# aaXBee.net
KiCad netlist of a schematic drawn in EAGLE
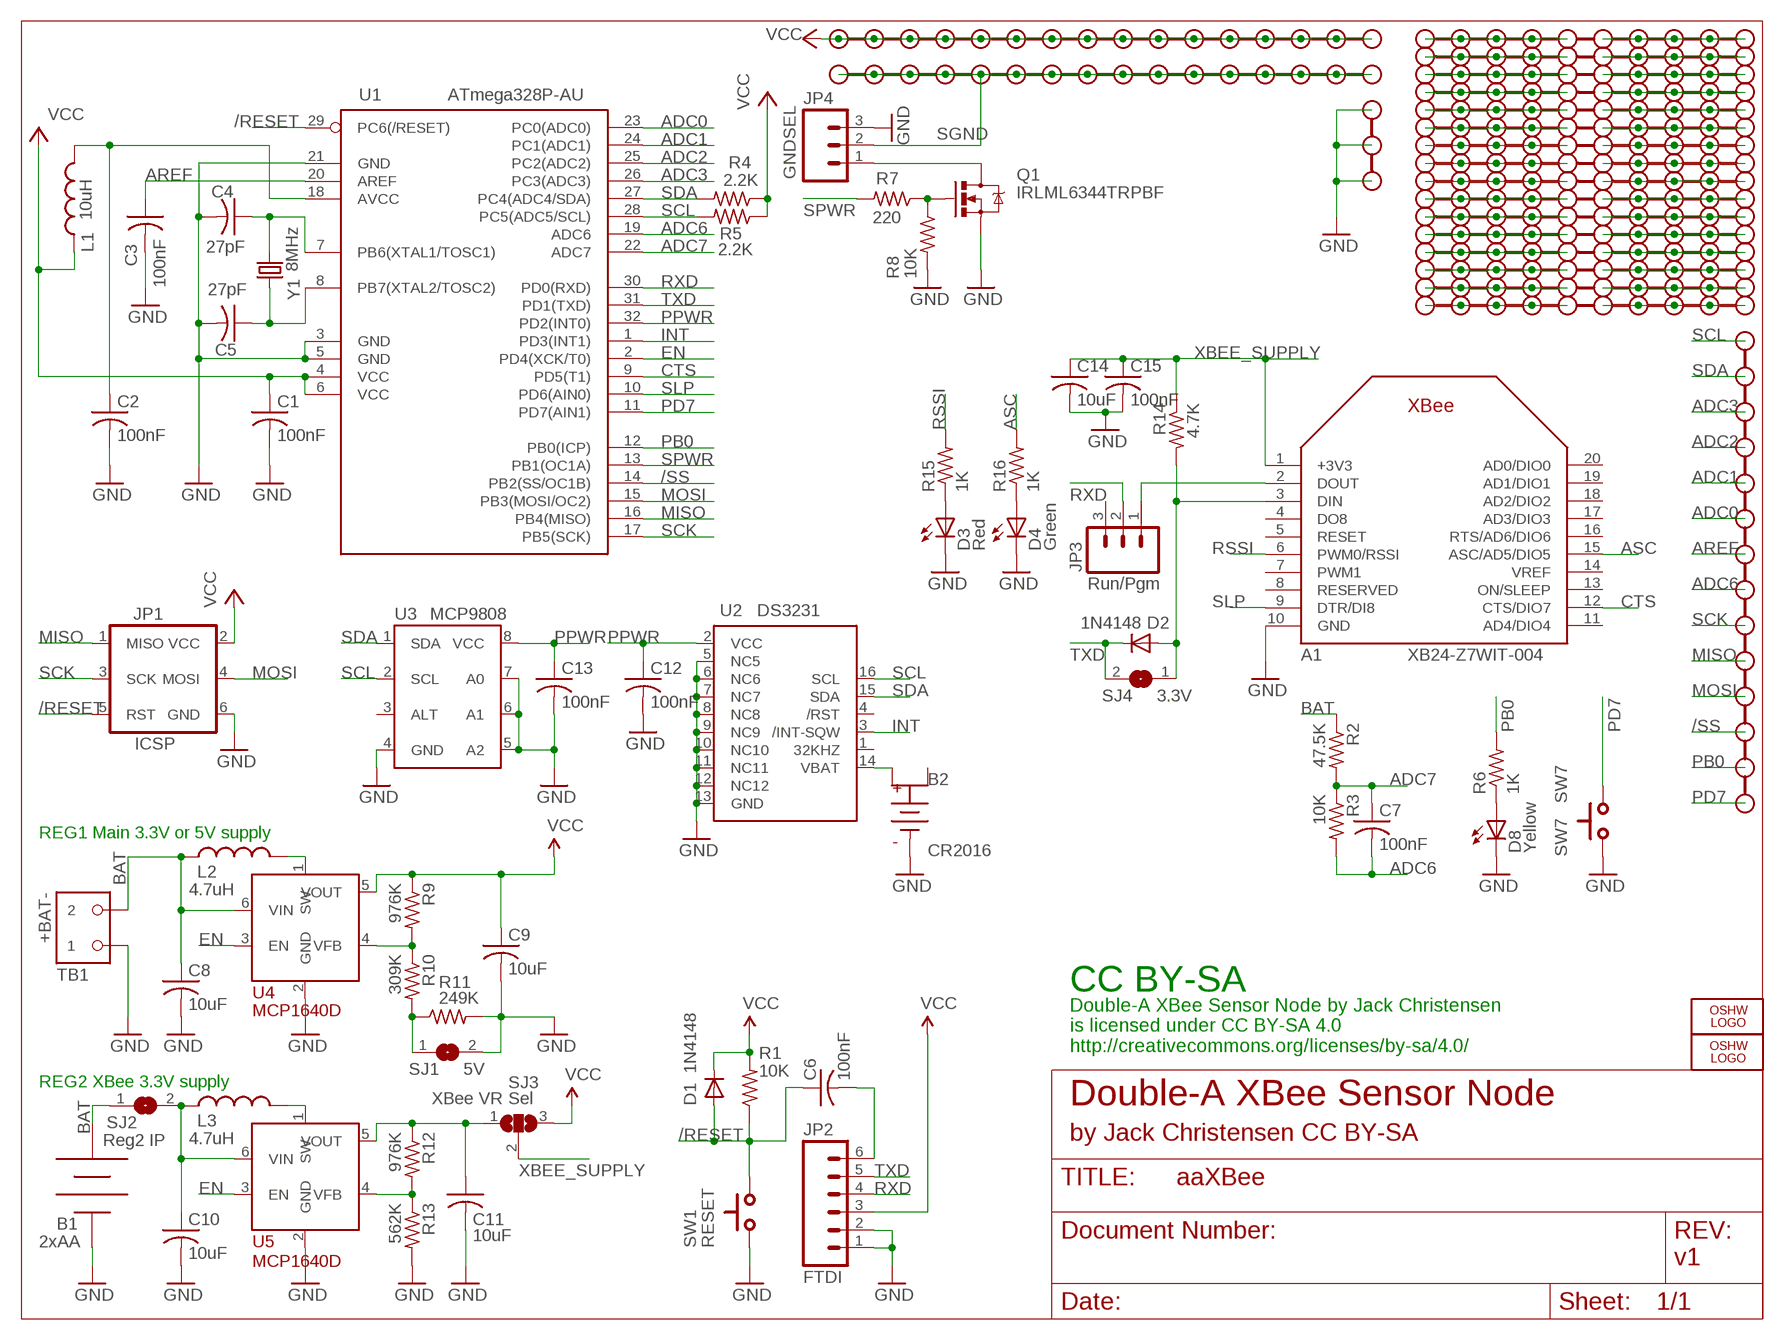
[diagram p0: schematic, sheet 1]

(export (version "E")
  (design (tool "Eeschema 10.0.6"))
  (components
    (comp (ref "A1")
      (value "XB24-Z7WIT-004")
      (footprint "eagle-import:XBEE_OVAL_PADS")
      (libsource (lib "eagle-import") (part "ULINK_XBEEOVALPADS"))
    )
    (comp (ref "B1")
      (value "2xAA")
      (footprint "eagle-import:KEYSTONE-2462-NO-HOLES")
      (libsource (lib "eagle-import") (part "BATTERY-2AANOHOLES"))
    )
    (comp (ref "B2")
      (value "CR2016")
      (footprint "eagle-import:BAT-HLD-002-SMT")
      (libsource (lib "eagle-import") (part "COIN-CELL-2016-SMT"))
    )
    (comp (ref "C1")
      (value "100nF")
      (footprint "eagle-import:M0805")
      (libsource (lib "eagle-import") (part "C-USM0805"))
    )
    (comp (ref "C2")
      (value "100nF")
      (footprint "eagle-import:M0805")
      (libsource (lib "eagle-import") (part "C-USM0805"))
    )
    (comp (ref "C3")
      (value "100nF")
      (footprint "eagle-import:M0805")
      (libsource (lib "eagle-import") (part "C-USM0805"))
    )
    (comp (ref "C4")
      (value "27pF")
      (footprint "eagle-import:M0805")
      (libsource (lib "eagle-import") (part "C-USM0805"))
    )
    (comp (ref "C5")
      (value "27pF")
      (footprint "eagle-import:M0805")
      (libsource (lib "eagle-import") (part "C-USM0805"))
    )
    (comp (ref "C6")
      (value "100nF")
      (footprint "eagle-import:M0805")
      (libsource (lib "eagle-import") (part "C-USM0805"))
    )
    (comp (ref "C7")
      (value "100nF")
      (footprint "eagle-import:M0805")
      (libsource (lib "eagle-import") (part "C-USM0805"))
    )
    (comp (ref "C8")
      (value "10uF")
      (footprint "eagle-import:M0805")
      (libsource (lib "eagle-import") (part "C-USM0805"))
    )
    (comp (ref "C9")
      (value "10uF")
      (footprint "eagle-import:M0805")
      (libsource (lib "eagle-import") (part "C-USM0805"))
    )
    (comp (ref "C10")
      (value "10uF")
      (footprint "eagle-import:M0805")
      (libsource (lib "eagle-import") (part "C-USM0805"))
    )
    (comp (ref "C11")
      (value "10uF")
      (footprint "eagle-import:M0805")
      (libsource (lib "eagle-import") (part "C-USM0805"))
    )
    (comp (ref "C12")
      (value "100nF")
      (footprint "eagle-import:M0805")
      (libsource (lib "eagle-import") (part "C-USM0805"))
    )
    (comp (ref "C13")
      (value "100nF")
      (footprint "eagle-import:M0805")
      (libsource (lib "eagle-import") (part "C-USM0805"))
    )
    (comp (ref "C14")
      (value "10uF")
      (footprint "eagle-import:M0805")
      (libsource (lib "eagle-import") (part "C-USM0805"))
    )
    (comp (ref "C15")
      (value "100nF")
      (footprint "eagle-import:M0805")
      (libsource (lib "eagle-import") (part "C-USM0805"))
    )
    (comp (ref "D1")
      (value "1N4148")
      (footprint "eagle-import:SOD-323F-A")
      (libsource (lib "eagle-import") (part "DIODESOD-323F-A"))
    )
    (comp (ref "D2")
      (value "1N4148")
      (footprint "eagle-import:SOD-323F-A")
      (libsource (lib "eagle-import") (part "DIODESOD-323F-A"))
    )
    (comp (ref "D3")
      (value "Red")
      (footprint "eagle-import:D0805A")
      (libsource (lib "eagle-import") (part "LEDD0805A"))
    )
    (comp (ref "D4")
      (value "Green")
      (footprint "eagle-import:D0805")
      (libsource (lib "eagle-import") (part "LEDD0805"))
    )
    (comp (ref "D8")
      (value "Yellow")
      (footprint "eagle-import:D0805A")
      (libsource (lib "eagle-import") (part "LEDD0805A"))
    )
    (comp (ref "JP1")
      (value "ICSP")
      (footprint "eagle-import:2X3_LOCK")
      (libsource (lib "eagle-import") (part "AVR_SPI_PRG_62X3_LOCK"))
    )
    (comp (ref "JP2")
      (value "FTDI")
      (footprint "eagle-import:1X06_LOCK")
      (libsource (lib "eagle-import") (part "M06LOCK"))
    )
    (comp (ref "JP3")
      (value "Run/Pgm")
      (footprint "eagle-import:1X03_LOCK")
      (libsource (lib "eagle-import") (part "M03LOCK"))
    )
    (comp (ref "JP4")
      (value "GNDSEL")
      (footprint "eagle-import:1X03_LOCK")
      (libsource (lib "eagle-import") (part "M03LOCK"))
    )
    (comp (ref "L1")
      (value "10uH")
      (footprint "eagle-import:M0805")
      (libsource (lib "eagle-import") (part "INDUCTORM0805"))
    )
    (comp (ref "L2")
      (value "4.7uH")
      (footprint "eagle-import:NRS4018")
      (libsource (lib "eagle-import") (part "INDUCTORNRS4018"))
    )
    (comp (ref "L3")
      (value "4.7uH")
      (footprint "eagle-import:NRS4018")
      (libsource (lib "eagle-import") (part "INDUCTORNRS4018"))
    )
    (comp (ref "LOGO1")
      (value "OSHW_LOGO_8MILX0150-NT")
      (footprint "eagle-import:OSHW_8X150_NOTEXT")
      (libsource (lib "eagle-import") (part "OSHW_LOGO_8MILX0150-NT"))
    )
    (comp (ref "LOGO2")
      (value "OSHW_LOGO_8MILX0150-NT")
      (footprint "eagle-import:OSHW_8X150_NOTEXT")
      (libsource (lib "eagle-import") (part "OSHW_LOGO_8MILX0150-NT"))
    )
    (comp (ref "PR1")
      (value "PROTO-10")
      (footprint "eagle-import:PROTO-10")
      (libsource (lib "eagle-import") (part "PROTO-10"))
    )
    (comp (ref "PR2")
      (value "PROTO-10")
      (footprint "eagle-import:PROTO-10")
      (libsource (lib "eagle-import") (part "PROTO-10"))
    )
    (comp (ref "PR3")
      (value "PROTO-10")
      (footprint "eagle-import:PROTO-10")
      (libsource (lib "eagle-import") (part "PROTO-10"))
    )
    (comp (ref "PR4")
      (value "PROTO-10")
      (footprint "eagle-import:PROTO-10")
      (libsource (lib "eagle-import") (part "PROTO-10"))
    )
    (comp (ref "PR5")
      (value "PROTO-10")
      (footprint "eagle-import:PROTO-10")
      (libsource (lib "eagle-import") (part "PROTO-10"))
    )
    (comp (ref "PR6")
      (value "PROTO-10")
      (footprint "eagle-import:PROTO-10")
      (libsource (lib "eagle-import") (part "PROTO-10"))
    )
    (comp (ref "PR7")
      (value "PROTO-10")
      (footprint "eagle-import:PROTO-10")
      (libsource (lib "eagle-import") (part "PROTO-10"))
    )
    (comp (ref "PR8")
      (value "PROTO-10")
      (footprint "eagle-import:PROTO-10")
      (libsource (lib "eagle-import") (part "PROTO-10"))
    )
    (comp (ref "PR9")
      (value "PROTO-10")
      (footprint "eagle-import:PROTO-10")
      (libsource (lib "eagle-import") (part "PROTO-10"))
    )
    (comp (ref "PR10")
      (value "PROTO-10")
      (footprint "eagle-import:PROTO-10")
      (libsource (lib "eagle-import") (part "PROTO-10"))
    )
    (comp (ref "PR11")
      (value "PROTO-10")
      (footprint "eagle-import:PROTO-10")
      (libsource (lib "eagle-import") (part "PROTO-10"))
    )
    (comp (ref "PR12")
      (value "PROTO-10")
      (footprint "eagle-import:PROTO-10")
      (libsource (lib "eagle-import") (part "PROTO-10"))
    )
    (comp (ref "PR13")
      (value "GND")
      (footprint "eagle-import:PROTO-3")
      (libsource (lib "eagle-import") (part "PROTO-3"))
    )
    (comp (ref "PR14")
      (value "PROTO-10")
      (footprint "eagle-import:PROTO-10")
      (libsource (lib "eagle-import") (part "PROTO-10"))
    )
    (comp (ref "PR15")
      (value "PROTO-10")
      (footprint "eagle-import:PROTO-10")
      (libsource (lib "eagle-import") (part "PROTO-10"))
    )
    (comp (ref "PR16")
      (value "PROTO-10")
      (footprint "eagle-import:PROTO-10")
      (libsource (lib "eagle-import") (part "PROTO-10"))
    )
    (comp (ref "PR17")
      (value "PROTO-10")
      (footprint "eagle-import:PROTO-10")
      (libsource (lib "eagle-import") (part "PROTO-10"))
    )
    (comp (ref "PR18")
      (value "Proto ground")
      (footprint "eagle-import:PROTO-16")
      (libsource (lib "eagle-import") (part "PROTO-16"))
    )
    (comp (ref "PR19")
      (value "Proto Vcc")
      (footprint "eagle-import:PROTO-16")
      (libsource (lib "eagle-import") (part "PROTO-16"))
    )
    (comp (ref "PR20")
      (value "Signals")
      (footprint "eagle-import:PROTO-14-NR")
      (libsource (lib "eagle-import") (part "PROTO-14NR"))
    )
    (comp (ref "Q1")
      (value "IRLML6344TRPBF")
      (footprint "eagle-import:SOT23")
      (libsource (lib "eagle-import") (part "MOSFET-NCHANNELSOT23"))
    )
    (comp (ref "R1")
      (value "10K")
      (footprint "eagle-import:M0805")
      (libsource (lib "eagle-import") (part "R-US_M0805"))
    )
    (comp (ref "R2")
      (value "47.5K")
      (footprint "eagle-import:M0805")
      (libsource (lib "eagle-import") (part "R-US_M0805"))
    )
    (comp (ref "R3")
      (value "10K")
      (footprint "eagle-import:M0805")
      (libsource (lib "eagle-import") (part "R-US_M0805"))
    )
    (comp (ref "R4")
      (value "2.2K")
      (footprint "eagle-import:M0805")
      (libsource (lib "eagle-import") (part "R-US_M0805"))
    )
    (comp (ref "R5")
      (value "2.2K")
      (footprint "eagle-import:M0805")
      (libsource (lib "eagle-import") (part "R-US_M0805"))
    )
    (comp (ref "R6")
      (value "1K")
      (footprint "eagle-import:M0805")
      (libsource (lib "eagle-import") (part "R-US_M0805"))
    )
    (comp (ref "R7")
      (value "220")
      (footprint "eagle-import:M0805")
      (libsource (lib "eagle-import") (part "R-US_M0805"))
    )
    (comp (ref "R8")
      (value "10K")
      (footprint "eagle-import:M0805")
      (libsource (lib "eagle-import") (part "R-US_M0805"))
    )
    (comp (ref "R9")
      (value "976K")
      (footprint "eagle-import:M0805")
      (libsource (lib "eagle-import") (part "R-US_M0805"))
    )
    (comp (ref "R10")
      (value "309K")
      (footprint "eagle-import:M0805")
      (libsource (lib "eagle-import") (part "R-US_M0805"))
    )
    (comp (ref "R11")
      (value "249K")
      (footprint "eagle-import:M0805")
      (libsource (lib "eagle-import") (part "R-US_M0805"))
    )
    (comp (ref "R12")
      (value "976K")
      (footprint "eagle-import:M0805")
      (libsource (lib "eagle-import") (part "R-US_M0805"))
    )
    (comp (ref "R13")
      (value "562K")
      (footprint "eagle-import:M0805")
      (libsource (lib "eagle-import") (part "R-US_M0805"))
    )
    (comp (ref "R14")
      (value "4.7K")
      (footprint "eagle-import:M0805")
      (libsource (lib "eagle-import") (part "R-US_M0805"))
    )
    (comp (ref "R15")
      (value "1K")
      (footprint "eagle-import:M0805")
      (libsource (lib "eagle-import") (part "R-US_M0805"))
    )
    (comp (ref "R16")
      (value "1K")
      (footprint "eagle-import:M0805")
      (libsource (lib "eagle-import") (part "R-US_M0805"))
    )
    (comp (ref "SJ1") (value "5V") (footprint "eagle-import:SJ") (libsource (lib "eagle-import") (part "SJ")))
    (comp (ref "SJ2")
      (value "Reg2 IP")
      (footprint "eagle-import:SJ")
      (libsource (lib "eagle-import") (part "SJ"))
    )
    (comp (ref "SJ3")
      (value "XBee VR Sel")
      (footprint "eagle-import:SJ_2")
      (libsource (lib "eagle-import") (part "SJ2W"))
    )
    (comp (ref "SJ4")
      (value "3.3V")
      (footprint "eagle-import:SJ")
      (libsource (lib "eagle-import") (part "SJ"))
    )
    (comp (ref "SW1")
      (value "RESET")
      (footprint "eagle-import:SWITCH-TACT-6X3.5-SMT")
      (libsource (lib "eagle-import") (part "SPST-NO-MCTACT-6X3.5-SMT"))
    )
    (comp (ref "SW7")
      (value "SW7")
      (footprint "eagle-import:SWITCH-TACT-6X3.5-SMT")
      (libsource (lib "eagle-import") (part "SPST-NO-MCTACT-6X3.5-SMT"))
    )
    (comp (ref "TB1")
      (value "+BAT-")
      (footprint "eagle-import:OST-TB-2-3.5MM")
      (libsource (lib "eagle-import") (part "OST-TB-23.5MM"))
    )
    (comp (ref "U1")
      (value "ATmega328P-AU")
      (footprint "eagle-import:TQFP32-08")
      (fields (field (name "MPN") "ATMEGA8-16AU"))
      (libsource (lib "eagle-import") (part "MEGA8-AI"))
    )
    (comp (ref "U2")
      (value "DS3231")
      (footprint "eagle-import:SO-16DW")
      (libsource (lib "eagle-import") (part "DS3231"))
    )
    (comp (ref "U3")
      (value "MCP9808")
      (footprint "eagle-import:MSOP8")
      (libsource (lib "eagle-import") (part "MCP9808"))
    )
    (comp (ref "U4")
      (value "MCP1640D")
      (footprint "eagle-import:SOT23-6")
      (libsource (lib "eagle-import") (part "MCP1640"))
    )
    (comp (ref "U5")
      (value "MCP1640D")
      (footprint "eagle-import:SOT23-6")
      (libsource (lib "eagle-import") (part "MCP1640"))
    )
    (comp (ref "Y1")
      (value "8MHz")
      (footprint "eagle-import:CRYSTAL-ABRACON-ABM2")
      (libsource (lib "eagle-import") (part "CRYSTALABM2"))
    )
  )
  (nets
    (net (code "1") (name "/ADC0") (class "Default")
      (node (ref "PR20") (pin "9") (pinfunction "9_9") (pintype "bidirectional"))
      (node (ref "U1") (pin "23") (pinfunction "PC0(ADC0)_23") (pintype "bidirectional"))
    )
    (net (code "2") (name "/ADC1") (class "Default")
      (node (ref "PR20") (pin "10") (pinfunction "10_10") (pintype "bidirectional"))
      (node (ref "U1") (pin "24") (pinfunction "PC1(ADC1)_24") (pintype "bidirectional"))
    )
    (net (code "3") (name "/ADC2") (class "Default")
      (node (ref "PR20") (pin "11") (pinfunction "11_11") (pintype "bidirectional"))
      (node (ref "U1") (pin "25") (pinfunction "PC2(ADC2)_25") (pintype "bidirectional"))
    )
    (net (code "4") (name "/ADC3") (class "Default")
      (node (ref "PR20") (pin "12") (pinfunction "12_12") (pintype "bidirectional"))
      (node (ref "U1") (pin "26") (pinfunction "PC3(ADC3)_26") (pintype "bidirectional"))
    )
    (net (code "5") (name "/ADC6") (class "Default")
      (node (ref "C7") (pin "2") (pinfunction "2_2") (pintype "passive"))
      (node (ref "PR20") (pin "7") (pinfunction "7_7") (pintype "bidirectional"))
      (node (ref "R3") (pin "2") (pinfunction "2_2") (pintype "passive"))
      (node (ref "U1") (pin "19") (pinfunction "ADC6_19") (pintype "bidirectional"))
    )
    (net (code "6") (name "/ADC7") (class "Default")
      (node (ref "C7") (pin "1") (pinfunction "1_1") (pintype "passive"))
      (node (ref "R2") (pin "2") (pinfunction "2_2") (pintype "passive"))
      (node (ref "R3") (pin "1") (pinfunction "1_1") (pintype "passive"))
      (node (ref "U1") (pin "22") (pinfunction "ADC7_22") (pintype "bidirectional"))
    )
    (net (code "7") (name "/AREF") (class "Default")
      (node (ref "C3") (pin "1") (pinfunction "1_1") (pintype "passive"))
      (node (ref "PR20") (pin "8") (pinfunction "8_8") (pintype "bidirectional"))
      (node (ref "U1") (pin "20") (pinfunction "AREF_20") (pintype "passive"))
    )
    (net (code "8") (name "/ASC") (class "Default")
      (node (ref "A1") (pin "15") (pinfunction "ASC/AD5/DIO5_15") (pintype "bidirectional"))
      (node (ref "R16") (pin "2") (pinfunction "2_2") (pintype "passive"))
    )
    (net (code "9") (name "/BAT") (class "Default")
      (node (ref "B1") (pin "POS") (pinfunction "POS_POS") (pintype "bidirectional"))
      (node (ref "C8") (pin "1") (pinfunction "1_1") (pintype "passive"))
      (node (ref "L2") (pin "P$1") (pinfunction "1_P$1") (pintype "passive"))
      (node (ref "R2") (pin "1") (pinfunction "1_1") (pintype "passive"))
      (node (ref "SJ2") (pin "1") (pinfunction "1_1") (pintype "passive"))
      (node (ref "TB1") (pin "P$2") (pinfunction "2_P$2") (pintype "passive"))
      (node (ref "U4") (pin "6") (pinfunction "VIN_6") (pintype "passive"))
    )
    (net (code "10") (name "/CTS") (class "Default")
      (node (ref "A1") (pin "12") (pinfunction "CTS/DIO7_12") (pintype "bidirectional"))
      (node (ref "U1") (pin "9") (pinfunction "PD5(T1)_9") (pintype "bidirectional"))
    )
    (net (code "11") (name "/EN") (class "Default")
      (node (ref "U1") (pin "2") (pinfunction "PD4(XCK/T0)_2") (pintype "bidirectional"))
      (node (ref "U4") (pin "3") (pinfunction "EN_3") (pintype "passive"))
      (node (ref "U5") (pin "3") (pinfunction "EN_3") (pintype "passive"))
    )
    (net (code "12") (name "/INT") (class "Default")
      (node (ref "U1") (pin "1") (pinfunction "PD3(INT1)_1") (pintype "bidirectional"))
      (node (ref "U2") (pin "3") (pinfunction "/INT-SQW_3") (pintype "bidirectional"))
    )
    (net (code "13") (name "/MISO") (class "Default")
      (node (ref "JP1") (pin "1") (pinfunction "MISO_1") (pintype "passive"))
      (node (ref "PR20") (pin "5") (pinfunction "5_5") (pintype "bidirectional"))
      (node (ref "U1") (pin "16") (pinfunction "PB4(MISO)_16") (pintype "bidirectional"))
    )
    (net (code "14") (name "/MOSI") (class "Default")
      (node (ref "JP1") (pin "4") (pinfunction "MOSI_4") (pintype "passive"))
      (node (ref "PR20") (pin "4") (pinfunction "4_4") (pintype "bidirectional"))
      (node (ref "U1") (pin "15") (pinfunction "PB3(MOSI/OC2)_15") (pintype "bidirectional"))
    )
    (net (code "15") (name "/PB0") (class "Default")
      (node (ref "PR20") (pin "2") (pinfunction "2_2") (pintype "bidirectional"))
      (node (ref "R6") (pin "2") (pinfunction "2_2") (pintype "passive"))
      (node (ref "U1") (pin "12") (pinfunction "PB0(ICP)_12") (pintype "bidirectional"))
    )
    (net (code "16") (name "/PD7") (class "Default")
      (node (ref "PR20") (pin "1") (pinfunction "1_1") (pintype "bidirectional"))
      (node (ref "SW7") (pin "P$1") (pinfunction "P$1_P$1") (pintype "bidirectional"))
      (node (ref "U1") (pin "11") (pinfunction "PD7(AIN1)_11") (pintype "bidirectional"))
    )
    (net (code "17") (name "/PPWR") (class "Default")
      (node (ref "C12") (pin "1") (pinfunction "1_1") (pintype "passive"))
      (node (ref "C13") (pin "1") (pinfunction "1_1") (pintype "passive"))
      (node (ref "U1") (pin "32") (pinfunction "PD2(INT0)_32") (pintype "bidirectional"))
      (node (ref "U2") (pin "2") (pinfunction "VCC_2") (pintype "bidirectional"))
      (node (ref "U3") (pin "8") (pinfunction "VCC_8") (pintype "passive"))
    )
    (net (code "18") (name "/RSSI") (class "Default")
      (node (ref "A1") (pin "6") (pinfunction "PWM0/RSSI_6") (pintype "bidirectional"))
      (node (ref "R15") (pin "2") (pinfunction "2_2") (pintype "passive"))
    )
    (net (code "19") (name "/RXD") (class "Default")
      (node (ref "JP2") (pin "4") (pinfunction "4_4") (pintype "passive"))
      (node (ref "JP3") (pin "2") (pinfunction "2_2") (pintype "passive"))
      (node (ref "U1") (pin "30") (pinfunction "PD0(RXD)_30") (pintype "bidirectional"))
    )
    (net (code "20") (name "/SCK") (class "Default")
      (node (ref "JP1") (pin "3") (pinfunction "SCK_3") (pintype "passive"))
      (node (ref "PR20") (pin "6") (pinfunction "6_6") (pintype "bidirectional"))
      (node (ref "U1") (pin "17") (pinfunction "PB5(SCK)_17") (pintype "bidirectional"))
    )
    (net (code "21") (name "/SCL") (class "Default")
      (node (ref "PR20") (pin "14") (pinfunction "14_14") (pintype "bidirectional"))
      (node (ref "R5") (pin "2") (pinfunction "2_2") (pintype "passive"))
      (node (ref "U1") (pin "28") (pinfunction "PC5(ADC5/SCL)_28") (pintype "bidirectional"))
      (node (ref "U2") (pin "16") (pinfunction "SCL_16") (pintype "bidirectional"))
      (node (ref "U3") (pin "2") (pinfunction "SCL_2") (pintype "passive"))
    )
    (net (code "22") (name "/SDA") (class "Default")
      (node (ref "PR20") (pin "13") (pinfunction "13_13") (pintype "bidirectional"))
      (node (ref "R4") (pin "2") (pinfunction "2_2") (pintype "passive"))
      (node (ref "U1") (pin "27") (pinfunction "PC4(ADC4/SDA)_27") (pintype "bidirectional"))
      (node (ref "U2") (pin "15") (pinfunction "SDA_15") (pintype "bidirectional"))
      (node (ref "U3") (pin "1") (pinfunction "SDA_1") (pintype "passive"))
    )
    (net (code "23") (name "/SGND") (class "Default")
      (node (ref "JP4") (pin "2") (pinfunction "2_2") (pintype "passive"))
      (node (ref "PR18") (pin "1") (pinfunction "1_1") (pintype "bidirectional"))
      (node (ref "PR18") (pin "10") (pinfunction "10_10") (pintype "bidirectional"))
      (node (ref "PR18") (pin "11") (pinfunction "11_11") (pintype "bidirectional"))
      (node (ref "PR18") (pin "12") (pinfunction "12_12") (pintype "bidirectional"))
      (node (ref "PR18") (pin "13") (pinfunction "13_13") (pintype "bidirectional"))
      (node (ref "PR18") (pin "14") (pinfunction "14_14") (pintype "bidirectional"))
      (node (ref "PR18") (pin "15") (pinfunction "15_15") (pintype "bidirectional"))
      (node (ref "PR18") (pin "16") (pinfunction "16_16") (pintype "bidirectional"))
      (node (ref "PR18") (pin "2") (pinfunction "2_2") (pintype "bidirectional"))
      (node (ref "PR18") (pin "3") (pinfunction "3_3") (pintype "bidirectional"))
      (node (ref "PR18") (pin "4") (pinfunction "4_4") (pintype "bidirectional"))
      (node (ref "PR18") (pin "5") (pinfunction "5_5") (pintype "bidirectional"))
      (node (ref "PR18") (pin "6") (pinfunction "6_6") (pintype "bidirectional"))
      (node (ref "PR18") (pin "7") (pinfunction "7_7") (pintype "bidirectional"))
      (node (ref "PR18") (pin "8") (pinfunction "8_8") (pintype "bidirectional"))
      (node (ref "PR18") (pin "9") (pinfunction "9_9") (pintype "bidirectional"))
    )
    (net (code "24") (name "/SLP") (class "Default")
      (node (ref "A1") (pin "9") (pinfunction "DTR/DI8_9") (pintype "bidirectional"))
      (node (ref "U1") (pin "10") (pinfunction "PD6(AIN0)_10") (pintype "bidirectional"))
    )
    (net (code "25") (name "/SPWR") (class "Default")
      (node (ref "R7") (pin "2") (pinfunction "2_2") (pintype "passive"))
      (node (ref "U1") (pin "13") (pinfunction "PB1(OC1A)_13") (pintype "bidirectional"))
    )
    (net (code "26") (name "/TXD") (class "Default")
      (node (ref "D2") (pin "K") (pinfunction "K_K") (pintype "passive"))
      (node (ref "JP2") (pin "5") (pinfunction "5_5") (pintype "passive"))
      (node (ref "SJ4") (pin "2") (pinfunction "2_2") (pintype "passive"))
      (node (ref "U1") (pin "31") (pinfunction "PD1(TXD)_31") (pintype "bidirectional"))
    )
    (net (code "27") (name "/XBEE_SUPPLY") (class "Default")
      (node (ref "A1") (pin "1") (pinfunction "+3V3_1") (pintype "bidirectional"))
      (node (ref "C14") (pin "1") (pinfunction "1_1") (pintype "passive"))
      (node (ref "C15") (pin "1") (pinfunction "1_1") (pintype "passive"))
      (node (ref "R14") (pin "1") (pinfunction "1_1") (pintype "passive"))
      (node (ref "SJ3") (pin "2") (pinfunction "2_2") (pintype "passive"))
    )
    (net (code "28") (name "/{slash}RESET") (class "Default")
      (node (ref "C6") (pin "1") (pinfunction "1_1") (pintype "passive"))
      (node (ref "D1") (pin "A") (pinfunction "A_A") (pintype "passive"))
      (node (ref "JP1") (pin "5") (pinfunction "RST_5") (pintype "passive"))
      (node (ref "R1") (pin "1") (pinfunction "1_1") (pintype "passive"))
      (node (ref "SW1") (pin "P$1") (pinfunction "P$1_P$1") (pintype "bidirectional"))
      (node (ref "U1") (pin "29") (pinfunction "PC6(/RESET)_29") (pintype "bidirectional"))
    )
    (net (code "29") (name "/{slash}SS") (class "Default")
      (node (ref "PR20") (pin "3") (pinfunction "3_3") (pintype "bidirectional"))
      (node (ref "U1") (pin "14") (pinfunction "PB2(SS/OC1B)_14") (pintype "bidirectional"))
    )
    (net (code "30") (name "GND") (class "Default")
      (node (ref "A1") (pin "10") (pinfunction "GND_10") (pintype "power_in"))
      (node (ref "B1") (pin "NEG") (pinfunction "NEG_NEG") (pintype "bidirectional"))
      (node (ref "B2") (pin "NEG") (pinfunction "B-_NEG") (pintype "passive"))
      (node (ref "C1") (pin "2") (pinfunction "2_2") (pintype "passive"))
      (node (ref "C10") (pin "2") (pinfunction "2_2") (pintype "passive"))
      (node (ref "C11") (pin "2") (pinfunction "2_2") (pintype "passive"))
      (node (ref "C12") (pin "2") (pinfunction "2_2") (pintype "passive"))
      (node (ref "C13") (pin "2") (pinfunction "2_2") (pintype "passive"))
      (node (ref "C14") (pin "2") (pinfunction "2_2") (pintype "passive"))
      (node (ref "C15") (pin "2") (pinfunction "2_2") (pintype "passive"))
      (node (ref "C2") (pin "2") (pinfunction "2_2") (pintype "passive"))
      (node (ref "C3") (pin "2") (pinfunction "2_2") (pintype "passive"))
      (node (ref "C4") (pin "2") (pinfunction "2_2") (pintype "passive"))
      (node (ref "C5") (pin "2") (pinfunction "2_2") (pintype "passive"))
      (node (ref "C8") (pin "2") (pinfunction "2_2") (pintype "passive"))
      (node (ref "C9") (pin "2") (pinfunction "2_2") (pintype "passive"))
      (node (ref "D3") (pin "K") (pinfunction "C_K") (pintype "passive"))
      (node (ref "D4") (pin "K") (pinfunction "C_K") (pintype "passive"))
      (node (ref "D8") (pin "K") (pinfunction "C_K") (pintype "passive"))
      (node (ref "JP1") (pin "6") (pinfunction "GND_6") (pintype "passive"))
      (node (ref "JP2") (pin "1") (pinfunction "1_1") (pintype "passive"))
      (node (ref "JP2") (pin "2") (pinfunction "2_2") (pintype "passive"))
      (node (ref "JP4") (pin "3") (pinfunction "3_3") (pintype "passive"))
      (node (ref "PR13") (pin "1") (pinfunction "1_1") (pintype "bidirectional"))
      (node (ref "PR13") (pin "2") (pinfunction "2_2") (pintype "bidirectional"))
      (node (ref "PR13") (pin "3") (pinfunction "3_3") (pintype "bidirectional"))
      (node (ref "Q1") (pin "2") (pinfunction "S_2") (pintype "passive"))
      (node (ref "R11") (pin "2") (pinfunction "2_2") (pintype "passive"))
      (node (ref "R13") (pin "2") (pinfunction "2_2") (pintype "passive"))
      (node (ref "R8") (pin "2") (pinfunction "2_2") (pintype "passive"))
      (node (ref "SJ1") (pin "2") (pinfunction "2_2") (pintype "passive"))
      (node (ref "SW1") (pin "P$2") (pinfunction "P$2_P$2") (pintype "bidirectional"))
      (node (ref "SW7") (pin "P$2") (pinfunction "P$2_P$2") (pintype "bidirectional"))
      (node (ref "TB1") (pin "P$1") (pinfunction "1_P$1") (pintype "passive"))
      (node (ref "U1") (pin "21") (pinfunction "GND_21") (pintype "power_in"))
      (node (ref "U1") (pin "3") (pinfunction "GND_3") (pintype "power_in"))
      (node (ref "U1") (pin "5") (pinfunction "GND_5") (pintype "power_in"))
      (node (ref "U2") (pin "10") (pinfunction "NC10_10") (pintype "bidirectional"))
      (node (ref "U2") (pin "11") (pinfunction "NC11_11") (pintype "bidirectional"))
      (node (ref "U2") (pin "12") (pinfunction "NC12_12") (pintype "bidirectional"))
      (node (ref "U2") (pin "13") (pinfunction "GND_13") (pintype "bidirectional"))
      (node (ref "U2") (pin "5") (pinfunction "NC5_5") (pintype "bidirectional"))
      (node (ref "U2") (pin "6") (pinfunction "NC6_6") (pintype "bidirectional"))
      (node (ref "U2") (pin "7") (pinfunction "NC7_7") (pintype "bidirectional"))
      (node (ref "U2") (pin "8") (pinfunction "NC8_8") (pintype "bidirectional"))
      (node (ref "U2") (pin "9") (pinfunction "NC9_9") (pintype "bidirectional"))
      (node (ref "U3") (pin "4") (pinfunction "GND_4") (pintype "passive"))
      (node (ref "U3") (pin "5") (pinfunction "A2_5") (pintype "passive"))
      (node (ref "U3") (pin "6") (pinfunction "A1_6") (pintype "passive"))
      (node (ref "U3") (pin "7") (pinfunction "A0_7") (pintype "passive"))
      (node (ref "U4") (pin "2") (pinfunction "GND_2") (pintype "passive"))
      (node (ref "U5") (pin "2") (pinfunction "GND_2") (pintype "passive"))
    )
    (net (code "31") (name "Net-(A1-DIN)") (class "Default")
      (node (ref "A1") (pin "3") (pinfunction "DIN_3") (pintype "input"))
      (node (ref "D2") (pin "A") (pinfunction "A_A") (pintype "passive"))
      (node (ref "R14") (pin "2") (pinfunction "2_2") (pintype "passive"))
      (node (ref "SJ4") (pin "1") (pinfunction "1_1") (pintype "passive"))
    )
    (net (code "32") (name "Net-(A1-DOUT)") (class "Default")
      (node (ref "A1") (pin "2") (pinfunction "DOUT_2") (pintype "output"))
      (node (ref "JP3") (pin "1") (pinfunction "1_1") (pintype "passive"))
    )
    (net (code "33") (name "Net-(C6-Pad2)") (class "Default")
      (node (ref "C6") (pin "2") (pinfunction "2_2") (pintype "passive"))
      (node (ref "JP2") (pin "6") (pinfunction "6_6") (pintype "passive"))
    )
    (net (code "34") (name "Net-(D3-PadA)") (class "Default")
      (node (ref "D3") (pin "A") (pinfunction "A_A") (pintype "passive"))
      (node (ref "R15") (pin "1") (pinfunction "1_1") (pintype "passive"))
    )
    (net (code "35") (name "Net-(D4-PadA)") (class "Default")
      (node (ref "D4") (pin "A") (pinfunction "A_A") (pintype "passive"))
      (node (ref "R16") (pin "1") (pinfunction "1_1") (pintype "passive"))
    )
    (net (code "36") (name "Net-(D8-PadA)") (class "Default")
      (node (ref "D8") (pin "A") (pinfunction "A_A") (pintype "passive"))
      (node (ref "R6") (pin "1") (pinfunction "1_1") (pintype "passive"))
    )
    (net (code "37") (name "Net-(L2-2)") (class "Default")
      (node (ref "L2") (pin "P$2") (pinfunction "2_P$2") (pintype "passive"))
      (node (ref "U4") (pin "1") (pinfunction "SW_1") (pintype "passive"))
    )
    (net (code "38") (name "Net-(L3-1)") (class "Default")
      (node (ref "C10") (pin "1") (pinfunction "1_1") (pintype "passive"))
      (node (ref "L3") (pin "P$1") (pinfunction "1_P$1") (pintype "passive"))
      (node (ref "SJ2") (pin "2") (pinfunction "2_2") (pintype "passive"))
      (node (ref "U5") (pin "6") (pinfunction "VIN_6") (pintype "passive"))
    )
    (net (code "39") (name "Net-(L3-2)") (class "Default")
      (node (ref "L3") (pin "P$2") (pinfunction "2_P$2") (pintype "passive"))
      (node (ref "U5") (pin "1") (pinfunction "SW_1") (pintype "passive"))
    )
    (net (code "40") (name "Net-(PR1-Pad1)") (class "Default")
      (node (ref "PR1") (pin "1") (pinfunction "1_1") (pintype "bidirectional"))
      (node (ref "PR1") (pin "2") (pinfunction "2_2") (pintype "bidirectional"))
      (node (ref "PR1") (pin "3") (pinfunction "3_3") (pintype "bidirectional"))
      (node (ref "PR1") (pin "4") (pinfunction "4_4") (pintype "bidirectional"))
      (node (ref "PR1") (pin "5") (pinfunction "5_5") (pintype "bidirectional"))
    )
    (net (code "41") (name "Net-(PR1-Pad10)") (class "Default")
      (node (ref "PR1") (pin "10") (pinfunction "10_10") (pintype "bidirectional"))
      (node (ref "PR1") (pin "6") (pinfunction "6_6") (pintype "bidirectional"))
      (node (ref "PR1") (pin "7") (pinfunction "7_7") (pintype "bidirectional"))
      (node (ref "PR1") (pin "8") (pinfunction "8_8") (pintype "bidirectional"))
      (node (ref "PR1") (pin "9") (pinfunction "9_9") (pintype "bidirectional"))
    )
    (net (code "42") (name "Net-(PR2-Pad1)") (class "Default")
      (node (ref "PR2") (pin "1") (pinfunction "1_1") (pintype "bidirectional"))
      (node (ref "PR2") (pin "2") (pinfunction "2_2") (pintype "bidirectional"))
      (node (ref "PR2") (pin "3") (pinfunction "3_3") (pintype "bidirectional"))
      (node (ref "PR2") (pin "4") (pinfunction "4_4") (pintype "bidirectional"))
      (node (ref "PR2") (pin "5") (pinfunction "5_5") (pintype "bidirectional"))
    )
    (net (code "43") (name "Net-(PR2-Pad10)") (class "Default")
      (node (ref "PR2") (pin "10") (pinfunction "10_10") (pintype "bidirectional"))
      (node (ref "PR2") (pin "6") (pinfunction "6_6") (pintype "bidirectional"))
      (node (ref "PR2") (pin "7") (pinfunction "7_7") (pintype "bidirectional"))
      (node (ref "PR2") (pin "8") (pinfunction "8_8") (pintype "bidirectional"))
      (node (ref "PR2") (pin "9") (pinfunction "9_9") (pintype "bidirectional"))
    )
    (net (code "44") (name "Net-(PR3-Pad1)") (class "Default")
      (node (ref "PR3") (pin "1") (pinfunction "1_1") (pintype "bidirectional"))
      (node (ref "PR3") (pin "2") (pinfunction "2_2") (pintype "bidirectional"))
      (node (ref "PR3") (pin "3") (pinfunction "3_3") (pintype "bidirectional"))
      (node (ref "PR3") (pin "4") (pinfunction "4_4") (pintype "bidirectional"))
      (node (ref "PR3") (pin "5") (pinfunction "5_5") (pintype "bidirectional"))
    )
    (net (code "45") (name "Net-(PR3-Pad10)") (class "Default")
      (node (ref "PR3") (pin "10") (pinfunction "10_10") (pintype "bidirectional"))
      (node (ref "PR3") (pin "6") (pinfunction "6_6") (pintype "bidirectional"))
      (node (ref "PR3") (pin "7") (pinfunction "7_7") (pintype "bidirectional"))
      (node (ref "PR3") (pin "8") (pinfunction "8_8") (pintype "bidirectional"))
      (node (ref "PR3") (pin "9") (pinfunction "9_9") (pintype "bidirectional"))
    )
    (net (code "46") (name "Net-(PR4-Pad1)") (class "Default")
      (node (ref "PR4") (pin "1") (pinfunction "1_1") (pintype "bidirectional"))
      (node (ref "PR4") (pin "2") (pinfunction "2_2") (pintype "bidirectional"))
      (node (ref "PR4") (pin "3") (pinfunction "3_3") (pintype "bidirectional"))
      (node (ref "PR4") (pin "4") (pinfunction "4_4") (pintype "bidirectional"))
      (node (ref "PR4") (pin "5") (pinfunction "5_5") (pintype "bidirectional"))
    )
    (net (code "47") (name "Net-(PR4-Pad10)") (class "Default")
      (node (ref "PR4") (pin "10") (pinfunction "10_10") (pintype "bidirectional"))
      (node (ref "PR4") (pin "6") (pinfunction "6_6") (pintype "bidirectional"))
      (node (ref "PR4") (pin "7") (pinfunction "7_7") (pintype "bidirectional"))
      (node (ref "PR4") (pin "8") (pinfunction "8_8") (pintype "bidirectional"))
      (node (ref "PR4") (pin "9") (pinfunction "9_9") (pintype "bidirectional"))
    )
    (net (code "48") (name "Net-(PR5-Pad1)") (class "Default")
      (node (ref "PR5") (pin "1") (pinfunction "1_1") (pintype "bidirectional"))
      (node (ref "PR5") (pin "2") (pinfunction "2_2") (pintype "bidirectional"))
      (node (ref "PR5") (pin "3") (pinfunction "3_3") (pintype "bidirectional"))
      (node (ref "PR5") (pin "4") (pinfunction "4_4") (pintype "bidirectional"))
      (node (ref "PR5") (pin "5") (pinfunction "5_5") (pintype "bidirectional"))
    )
    (net (code "49") (name "Net-(PR5-Pad10)") (class "Default")
      (node (ref "PR5") (pin "10") (pinfunction "10_10") (pintype "bidirectional"))
      (node (ref "PR5") (pin "6") (pinfunction "6_6") (pintype "bidirectional"))
      (node (ref "PR5") (pin "7") (pinfunction "7_7") (pintype "bidirectional"))
      (node (ref "PR5") (pin "8") (pinfunction "8_8") (pintype "bidirectional"))
      (node (ref "PR5") (pin "9") (pinfunction "9_9") (pintype "bidirectional"))
    )
    (net (code "50") (name "Net-(PR6-Pad1)") (class "Default")
      (node (ref "PR6") (pin "1") (pinfunction "1_1") (pintype "bidirectional"))
      (node (ref "PR6") (pin "2") (pinfunction "2_2") (pintype "bidirectional"))
      (node (ref "PR6") (pin "3") (pinfunction "3_3") (pintype "bidirectional"))
      (node (ref "PR6") (pin "4") (pinfunction "4_4") (pintype "bidirectional"))
      (node (ref "PR6") (pin "5") (pinfunction "5_5") (pintype "bidirectional"))
    )
    (net (code "51") (name "Net-(PR6-Pad10)") (class "Default")
      (node (ref "PR6") (pin "10") (pinfunction "10_10") (pintype "bidirectional"))
      (node (ref "PR6") (pin "6") (pinfunction "6_6") (pintype "bidirectional"))
      (node (ref "PR6") (pin "7") (pinfunction "7_7") (pintype "bidirectional"))
      (node (ref "PR6") (pin "8") (pinfunction "8_8") (pintype "bidirectional"))
      (node (ref "PR6") (pin "9") (pinfunction "9_9") (pintype "bidirectional"))
    )
    (net (code "52") (name "Net-(PR7-Pad1)") (class "Default")
      (node (ref "PR7") (pin "1") (pinfunction "1_1") (pintype "bidirectional"))
      (node (ref "PR7") (pin "2") (pinfunction "2_2") (pintype "bidirectional"))
      (node (ref "PR7") (pin "3") (pinfunction "3_3") (pintype "bidirectional"))
      (node (ref "PR7") (pin "4") (pinfunction "4_4") (pintype "bidirectional"))
      (node (ref "PR7") (pin "5") (pinfunction "5_5") (pintype "bidirectional"))
    )
    (net (code "53") (name "Net-(PR7-Pad10)") (class "Default")
      (node (ref "PR7") (pin "10") (pinfunction "10_10") (pintype "bidirectional"))
      (node (ref "PR7") (pin "6") (pinfunction "6_6") (pintype "bidirectional"))
      (node (ref "PR7") (pin "7") (pinfunction "7_7") (pintype "bidirectional"))
      (node (ref "PR7") (pin "8") (pinfunction "8_8") (pintype "bidirectional"))
      (node (ref "PR7") (pin "9") (pinfunction "9_9") (pintype "bidirectional"))
    )
    (net (code "54") (name "Net-(PR8-Pad1)") (class "Default")
      (node (ref "PR8") (pin "1") (pinfunction "1_1") (pintype "bidirectional"))
      (node (ref "PR8") (pin "2") (pinfunction "2_2") (pintype "bidirectional"))
      (node (ref "PR8") (pin "3") (pinfunction "3_3") (pintype "bidirectional"))
      (node (ref "PR8") (pin "4") (pinfunction "4_4") (pintype "bidirectional"))
      (node (ref "PR8") (pin "5") (pinfunction "5_5") (pintype "bidirectional"))
    )
    (net (code "55") (name "Net-(PR8-Pad10)") (class "Default")
      (node (ref "PR8") (pin "10") (pinfunction "10_10") (pintype "bidirectional"))
      (node (ref "PR8") (pin "6") (pinfunction "6_6") (pintype "bidirectional"))
      (node (ref "PR8") (pin "7") (pinfunction "7_7") (pintype "bidirectional"))
      (node (ref "PR8") (pin "8") (pinfunction "8_8") (pintype "bidirectional"))
      (node (ref "PR8") (pin "9") (pinfunction "9_9") (pintype "bidirectional"))
    )
    (net (code "56") (name "Net-(PR9-Pad1)") (class "Default")
      (node (ref "PR9") (pin "1") (pinfunction "1_1") (pintype "bidirectional"))
      (node (ref "PR9") (pin "2") (pinfunction "2_2") (pintype "bidirectional"))
      (node (ref "PR9") (pin "3") (pinfunction "3_3") (pintype "bidirectional"))
      (node (ref "PR9") (pin "4") (pinfunction "4_4") (pintype "bidirectional"))
      (node (ref "PR9") (pin "5") (pinfunction "5_5") (pintype "bidirectional"))
    )
    (net (code "57") (name "Net-(PR9-Pad10)") (class "Default")
      (node (ref "PR9") (pin "10") (pinfunction "10_10") (pintype "bidirectional"))
      (node (ref "PR9") (pin "6") (pinfunction "6_6") (pintype "bidirectional"))
      (node (ref "PR9") (pin "7") (pinfunction "7_7") (pintype "bidirectional"))
      (node (ref "PR9") (pin "8") (pinfunction "8_8") (pintype "bidirectional"))
      (node (ref "PR9") (pin "9") (pinfunction "9_9") (pintype "bidirectional"))
    )
    (net (code "58") (name "Net-(PR10-Pad1)") (class "Default")
      (node (ref "PR10") (pin "1") (pinfunction "1_1") (pintype "bidirectional"))
      (node (ref "PR10") (pin "2") (pinfunction "2_2") (pintype "bidirectional"))
      (node (ref "PR10") (pin "3") (pinfunction "3_3") (pintype "bidirectional"))
      (node (ref "PR10") (pin "4") (pinfunction "4_4") (pintype "bidirectional"))
      (node (ref "PR10") (pin "5") (pinfunction "5_5") (pintype "bidirectional"))
    )
    (net (code "59") (name "Net-(PR10-Pad10)") (class "Default")
      (node (ref "PR10") (pin "10") (pinfunction "10_10") (pintype "bidirectional"))
      (node (ref "PR10") (pin "6") (pinfunction "6_6") (pintype "bidirectional"))
      (node (ref "PR10") (pin "7") (pinfunction "7_7") (pintype "bidirectional"))
      (node (ref "PR10") (pin "8") (pinfunction "8_8") (pintype "bidirectional"))
      (node (ref "PR10") (pin "9") (pinfunction "9_9") (pintype "bidirectional"))
    )
    (net (code "60") (name "Net-(PR11-Pad1)") (class "Default")
      (node (ref "PR11") (pin "1") (pinfunction "1_1") (pintype "bidirectional"))
      (node (ref "PR11") (pin "2") (pinfunction "2_2") (pintype "bidirectional"))
      (node (ref "PR11") (pin "3") (pinfunction "3_3") (pintype "bidirectional"))
      (node (ref "PR11") (pin "4") (pinfunction "4_4") (pintype "bidirectional"))
      (node (ref "PR11") (pin "5") (pinfunction "5_5") (pintype "bidirectional"))
    )
    (net (code "61") (name "Net-(PR11-Pad10)") (class "Default")
      (node (ref "PR11") (pin "10") (pinfunction "10_10") (pintype "bidirectional"))
      (node (ref "PR11") (pin "6") (pinfunction "6_6") (pintype "bidirectional"))
      (node (ref "PR11") (pin "7") (pinfunction "7_7") (pintype "bidirectional"))
      (node (ref "PR11") (pin "8") (pinfunction "8_8") (pintype "bidirectional"))
      (node (ref "PR11") (pin "9") (pinfunction "9_9") (pintype "bidirectional"))
    )
    (net (code "62") (name "Net-(PR12-Pad1)") (class "Default")
      (node (ref "PR12") (pin "1") (pinfunction "1_1") (pintype "bidirectional"))
      (node (ref "PR12") (pin "2") (pinfunction "2_2") (pintype "bidirectional"))
      (node (ref "PR12") (pin "3") (pinfunction "3_3") (pintype "bidirectional"))
      (node (ref "PR12") (pin "4") (pinfunction "4_4") (pintype "bidirectional"))
      (node (ref "PR12") (pin "5") (pinfunction "5_5") (pintype "bidirectional"))
    )
    (net (code "63") (name "Net-(PR12-Pad10)") (class "Default")
      (node (ref "PR12") (pin "10") (pinfunction "10_10") (pintype "bidirectional"))
      (node (ref "PR12") (pin "6") (pinfunction "6_6") (pintype "bidirectional"))
      (node (ref "PR12") (pin "7") (pinfunction "7_7") (pintype "bidirectional"))
      (node (ref "PR12") (pin "8") (pinfunction "8_8") (pintype "bidirectional"))
      (node (ref "PR12") (pin "9") (pinfunction "9_9") (pintype "bidirectional"))
    )
    (net (code "64") (name "Net-(PR14-Pad1)") (class "Default")
      (node (ref "PR14") (pin "1") (pinfunction "1_1") (pintype "bidirectional"))
      (node (ref "PR14") (pin "2") (pinfunction "2_2") (pintype "bidirectional"))
      (node (ref "PR14") (pin "3") (pinfunction "3_3") (pintype "bidirectional"))
      (node (ref "PR14") (pin "4") (pinfunction "4_4") (pintype "bidirectional"))
      (node (ref "PR14") (pin "5") (pinfunction "5_5") (pintype "bidirectional"))
    )
    (net (code "65") (name "Net-(PR14-Pad10)") (class "Default")
      (node (ref "PR14") (pin "10") (pinfunction "10_10") (pintype "bidirectional"))
      (node (ref "PR14") (pin "6") (pinfunction "6_6") (pintype "bidirectional"))
      (node (ref "PR14") (pin "7") (pinfunction "7_7") (pintype "bidirectional"))
      (node (ref "PR14") (pin "8") (pinfunction "8_8") (pintype "bidirectional"))
      (node (ref "PR14") (pin "9") (pinfunction "9_9") (pintype "bidirectional"))
    )
    (net (code "66") (name "Net-(PR15-Pad1)") (class "Default")
      (node (ref "PR15") (pin "1") (pinfunction "1_1") (pintype "bidirectional"))
      (node (ref "PR15") (pin "2") (pinfunction "2_2") (pintype "bidirectional"))
      (node (ref "PR15") (pin "3") (pinfunction "3_3") (pintype "bidirectional"))
      (node (ref "PR15") (pin "4") (pinfunction "4_4") (pintype "bidirectional"))
      (node (ref "PR15") (pin "5") (pinfunction "5_5") (pintype "bidirectional"))
    )
    (net (code "67") (name "Net-(PR15-Pad10)") (class "Default")
      (node (ref "PR15") (pin "10") (pinfunction "10_10") (pintype "bidirectional"))
      (node (ref "PR15") (pin "6") (pinfunction "6_6") (pintype "bidirectional"))
      (node (ref "PR15") (pin "7") (pinfunction "7_7") (pintype "bidirectional"))
      (node (ref "PR15") (pin "8") (pinfunction "8_8") (pintype "bidirectional"))
      (node (ref "PR15") (pin "9") (pinfunction "9_9") (pintype "bidirectional"))
    )
    (net (code "68") (name "Net-(PR16-Pad1)") (class "Default")
      (node (ref "PR16") (pin "1") (pinfunction "1_1") (pintype "bidirectional"))
      (node (ref "PR16") (pin "2") (pinfunction "2_2") (pintype "bidirectional"))
      (node (ref "PR16") (pin "3") (pinfunction "3_3") (pintype "bidirectional"))
      (node (ref "PR16") (pin "4") (pinfunction "4_4") (pintype "bidirectional"))
      (node (ref "PR16") (pin "5") (pinfunction "5_5") (pintype "bidirectional"))
    )
    (net (code "69") (name "Net-(PR16-Pad10)") (class "Default")
      (node (ref "PR16") (pin "10") (pinfunction "10_10") (pintype "bidirectional"))
      (node (ref "PR16") (pin "6") (pinfunction "6_6") (pintype "bidirectional"))
      (node (ref "PR16") (pin "7") (pinfunction "7_7") (pintype "bidirectional"))
      (node (ref "PR16") (pin "8") (pinfunction "8_8") (pintype "bidirectional"))
      (node (ref "PR16") (pin "9") (pinfunction "9_9") (pintype "bidirectional"))
    )
    (net (code "70") (name "Net-(PR17-Pad1)") (class "Default")
      (node (ref "PR17") (pin "1") (pinfunction "1_1") (pintype "bidirectional"))
      (node (ref "PR17") (pin "2") (pinfunction "2_2") (pintype "bidirectional"))
      (node (ref "PR17") (pin "3") (pinfunction "3_3") (pintype "bidirectional"))
      (node (ref "PR17") (pin "4") (pinfunction "4_4") (pintype "bidirectional"))
      (node (ref "PR17") (pin "5") (pinfunction "5_5") (pintype "bidirectional"))
    )
    (net (code "71") (name "Net-(PR17-Pad10)") (class "Default")
      (node (ref "PR17") (pin "10") (pinfunction "10_10") (pintype "bidirectional"))
      (node (ref "PR17") (pin "6") (pinfunction "6_6") (pintype "bidirectional"))
      (node (ref "PR17") (pin "7") (pinfunction "7_7") (pintype "bidirectional"))
      (node (ref "PR17") (pin "8") (pinfunction "8_8") (pintype "bidirectional"))
      (node (ref "PR17") (pin "9") (pinfunction "9_9") (pintype "bidirectional"))
    )
    (net (code "72") (name "Net-(Q1-D)") (class "Default")
      (node (ref "JP4") (pin "1") (pinfunction "1_1") (pintype "passive"))
      (node (ref "Q1") (pin "3") (pinfunction "D_3") (pintype "passive"))
    )
    (net (code "73") (name "Net-(Q1-G)") (class "Default")
      (node (ref "Q1") (pin "1") (pinfunction "G_1") (pintype "passive"))
      (node (ref "R7") (pin "1") (pinfunction "1_1") (pintype "passive"))
      (node (ref "R8") (pin "1") (pinfunction "1_1") (pintype "passive"))
    )
    (net (code "74") (name "Net-(R10-Pad2)") (class "Default")
      (node (ref "R10") (pin "2") (pinfunction "2_2") (pintype "passive"))
      (node (ref "R11") (pin "1") (pinfunction "1_1") (pintype "passive"))
      (node (ref "SJ1") (pin "1") (pinfunction "1_1") (pintype "passive"))
    )
    (net (code "75") (name "Net-(U1-AVCC)") (class "Default")
      (node (ref "C2") (pin "1") (pinfunction "1_1") (pintype "passive"))
      (node (ref "L1") (pin "2") (pinfunction "2_2") (pintype "passive"))
      (node (ref "U1") (pin "18") (pinfunction "AVCC_18") (pintype "power_in"))
    )
    (net (code "76") (name "Net-(U1-PB6(XTAL1{slash}TOSC1))") (class "Default")
      (node (ref "C4") (pin "1") (pinfunction "1_1") (pintype "passive"))
      (node (ref "U1") (pin "7") (pinfunction "PB6(XTAL1/TOSC1)_7") (pintype "bidirectional"))
      (node (ref "Y1") (pin "P$2") (pinfunction "2_P$2") (pintype "passive"))
    )
    (net (code "77") (name "Net-(U1-PB7(XTAL2{slash}TOSC2))") (class "Default")
      (node (ref "C5") (pin "1") (pinfunction "1_1") (pintype "passive"))
      (node (ref "U1") (pin "8") (pinfunction "PB7(XTAL2/TOSC2)_8") (pintype "bidirectional"))
      (node (ref "Y1") (pin "P$1") (pinfunction "1_P$1") (pintype "passive"))
    )
    (net (code "78") (name "Net-(U2-VBAT)") (class "Default")
      (node (ref "B2") (pin "POS1") (pinfunction "POS1_POS1") (pintype "passive"))
      (node (ref "U2") (pin "14") (pinfunction "VBAT_14") (pintype "bidirectional"))
    )
    (net (code "79") (name "Net-(U4-VFB)") (class "Default")
      (node (ref "R10") (pin "1") (pinfunction "1_1") (pintype "passive"))
      (node (ref "R9") (pin "2") (pinfunction "2_2") (pintype "passive"))
      (node (ref "U4") (pin "4") (pinfunction "VFB_4") (pintype "passive"))
    )
    (net (code "80") (name "Net-(U5-VFB)") (class "Default")
      (node (ref "R12") (pin "2") (pinfunction "2_2") (pintype "passive"))
      (node (ref "R13") (pin "1") (pinfunction "1_1") (pintype "passive"))
      (node (ref "U5") (pin "4") (pinfunction "VFB_4") (pintype "passive"))
    )
    (net (code "81") (name "Net-(U5-VOUT)") (class "Default")
      (node (ref "C11") (pin "1") (pinfunction "1_1") (pintype "passive"))
      (node (ref "R12") (pin "1") (pinfunction "1_1") (pintype "passive"))
      (node (ref "SJ3") (pin "1") (pinfunction "1_1") (pintype "passive"))
      (node (ref "U5") (pin "5") (pinfunction "VOUT_5") (pintype "passive"))
    )
    (net (code "82") (name "VCC") (class "Default")
      (node (ref "C1") (pin "1") (pinfunction "1_1") (pintype "passive"))
      (node (ref "C9") (pin "1") (pinfunction "1_1") (pintype "passive"))
      (node (ref "D1") (pin "K") (pinfunction "K_K") (pintype "passive"))
      (node (ref "JP1") (pin "2") (pinfunction "VCC_2") (pintype "passive"))
      (node (ref "JP2") (pin "3") (pinfunction "3_3") (pintype "passive"))
      (node (ref "L1") (pin "1") (pinfunction "1_1") (pintype "passive"))
      (node (ref "PR19") (pin "1") (pinfunction "1_1") (pintype "bidirectional"))
      (node (ref "PR19") (pin "10") (pinfunction "10_10") (pintype "bidirectional"))
      (node (ref "PR19") (pin "11") (pinfunction "11_11") (pintype "bidirectional"))
      (node (ref "PR19") (pin "12") (pinfunction "12_12") (pintype "bidirectional"))
      (node (ref "PR19") (pin "13") (pinfunction "13_13") (pintype "bidirectional"))
      (node (ref "PR19") (pin "14") (pinfunction "14_14") (pintype "bidirectional"))
      (node (ref "PR19") (pin "15") (pinfunction "15_15") (pintype "bidirectional"))
      (node (ref "PR19") (pin "16") (pinfunction "16_16") (pintype "bidirectional"))
      (node (ref "PR19") (pin "2") (pinfunction "2_2") (pintype "bidirectional"))
      (node (ref "PR19") (pin "3") (pinfunction "3_3") (pintype "bidirectional"))
      (node (ref "PR19") (pin "4") (pinfunction "4_4") (pintype "bidirectional"))
      (node (ref "PR19") (pin "5") (pinfunction "5_5") (pintype "bidirectional"))
      (node (ref "PR19") (pin "6") (pinfunction "6_6") (pintype "bidirectional"))
      (node (ref "PR19") (pin "7") (pinfunction "7_7") (pintype "bidirectional"))
      (node (ref "PR19") (pin "8") (pinfunction "8_8") (pintype "bidirectional"))
      (node (ref "PR19") (pin "9") (pinfunction "9_9") (pintype "bidirectional"))
      (node (ref "R1") (pin "2") (pinfunction "2_2") (pintype "passive"))
      (node (ref "R4") (pin "1") (pinfunction "1_1") (pintype "passive"))
      (node (ref "R5") (pin "1") (pinfunction "1_1") (pintype "passive"))
      (node (ref "R9") (pin "1") (pinfunction "1_1") (pintype "passive"))
      (node (ref "SJ3") (pin "3") (pinfunction "3_3") (pintype "passive"))
      (node (ref "U1") (pin "4") (pinfunction "VCC_4") (pintype "power_in"))
      (node (ref "U1") (pin "6") (pinfunction "VCC_6") (pintype "power_in"))
      (node (ref "U4") (pin "5") (pinfunction "VOUT_5") (pintype "passive"))
    )
    (net (code "83") (name "unconnected-(A1-AD0{slash}DIO0-Pad20)") (class "Default")
      (node (ref "A1") (pin "20") (pinfunction "AD0/DIO0_20") (pintype "bidirectional"))
    )
    (net (code "84") (name "unconnected-(A1-AD1{slash}DIO1-Pad19)") (class "Default")
      (node (ref "A1") (pin "19") (pinfunction "AD1/DIO1_19") (pintype "bidirectional"))
    )
    (net (code "85") (name "unconnected-(A1-AD2{slash}DIO2-Pad18)") (class "Default")
      (node (ref "A1") (pin "18") (pinfunction "AD2/DIO2_18") (pintype "bidirectional"))
    )
    (net (code "86") (name "unconnected-(A1-AD3{slash}DIO3-Pad17)") (class "Default")
      (node (ref "A1") (pin "17") (pinfunction "AD3/DIO3_17") (pintype "bidirectional"))
    )
    (net (code "87") (name "unconnected-(A1-AD4{slash}DIO4-Pad11)") (class "Default")
      (node (ref "A1") (pin "11") (pinfunction "AD4/DIO4_11") (pintype "bidirectional"))
    )
    (net (code "88") (name "unconnected-(A1-DO8-Pad4)") (class "Default")
      (node (ref "A1") (pin "4") (pinfunction "DO8_4") (pintype "output"))
    )
    (net (code "89") (name "unconnected-(A1-ON{slash}SLEEP-Pad13)") (class "Default")
      (node (ref "A1") (pin "13") (pinfunction "ON/SLEEP_13") (pintype "output"))
    )
    (net (code "90") (name "unconnected-(A1-PWM1-Pad7)") (class "Default")
      (node (ref "A1") (pin "7") (pinfunction "PWM1_7") (pintype "bidirectional"))
    )
    (net (code "91") (name "unconnected-(A1-RESERVED-Pad8)") (class "Default")
      (node (ref "A1") (pin "8") (pinfunction "RESERVED_8") (pintype "no_connect"))
    )
    (net (code "92") (name "unconnected-(A1-RESET-Pad5)") (class "Default")
      (node (ref "A1") (pin "5") (pinfunction "RESET_5") (pintype "bidirectional"))
    )
    (net (code "93") (name "unconnected-(A1-RTS{slash}AD6{slash}DIO6-Pad16)") (class "Default")
      (node (ref "A1") (pin "16") (pinfunction "RTS/AD6/DIO6_16") (pintype "bidirectional"))
    )
    (net (code "94") (name "unconnected-(A1-VREF-Pad14)") (class "Default")
      (node (ref "A1") (pin "14") (pinfunction "VREF_14") (pintype "bidirectional"))
    )
    (net (code "95") (name "unconnected-(B2-PadPOS2)") (class "Default")
      (node (ref "B2") (pin "POS2") (pinfunction "POS2_POS2") (pintype "passive"))
    )
    (net (code "96") (name "unconnected-(JP3-Pad3)") (class "Default")
      (node (ref "JP3") (pin "3") (pinfunction "3_3") (pintype "passive"))
    )
    (net (code "97") (name "unconnected-(U2-32KHZ-Pad1)") (class "Default")
      (node (ref "U2") (pin "1") (pinfunction "32KHZ_1") (pintype "bidirectional"))
    )
    (net (code "98") (name "unconnected-(U2-{slash}RST-Pad4)") (class "Default")
      (node (ref "U2") (pin "4") (pinfunction "/RST_4") (pintype "bidirectional"))
    )
    (net (code "99") (name "unconnected-(U3-ALT-Pad3)") (class "Default")
      (node (ref "U3") (pin "3") (pinfunction "ALT_3") (pintype "passive"))
    )
  )
)
